# telem_board.net
KiCad netlist of a schematic drawn in EAGLE
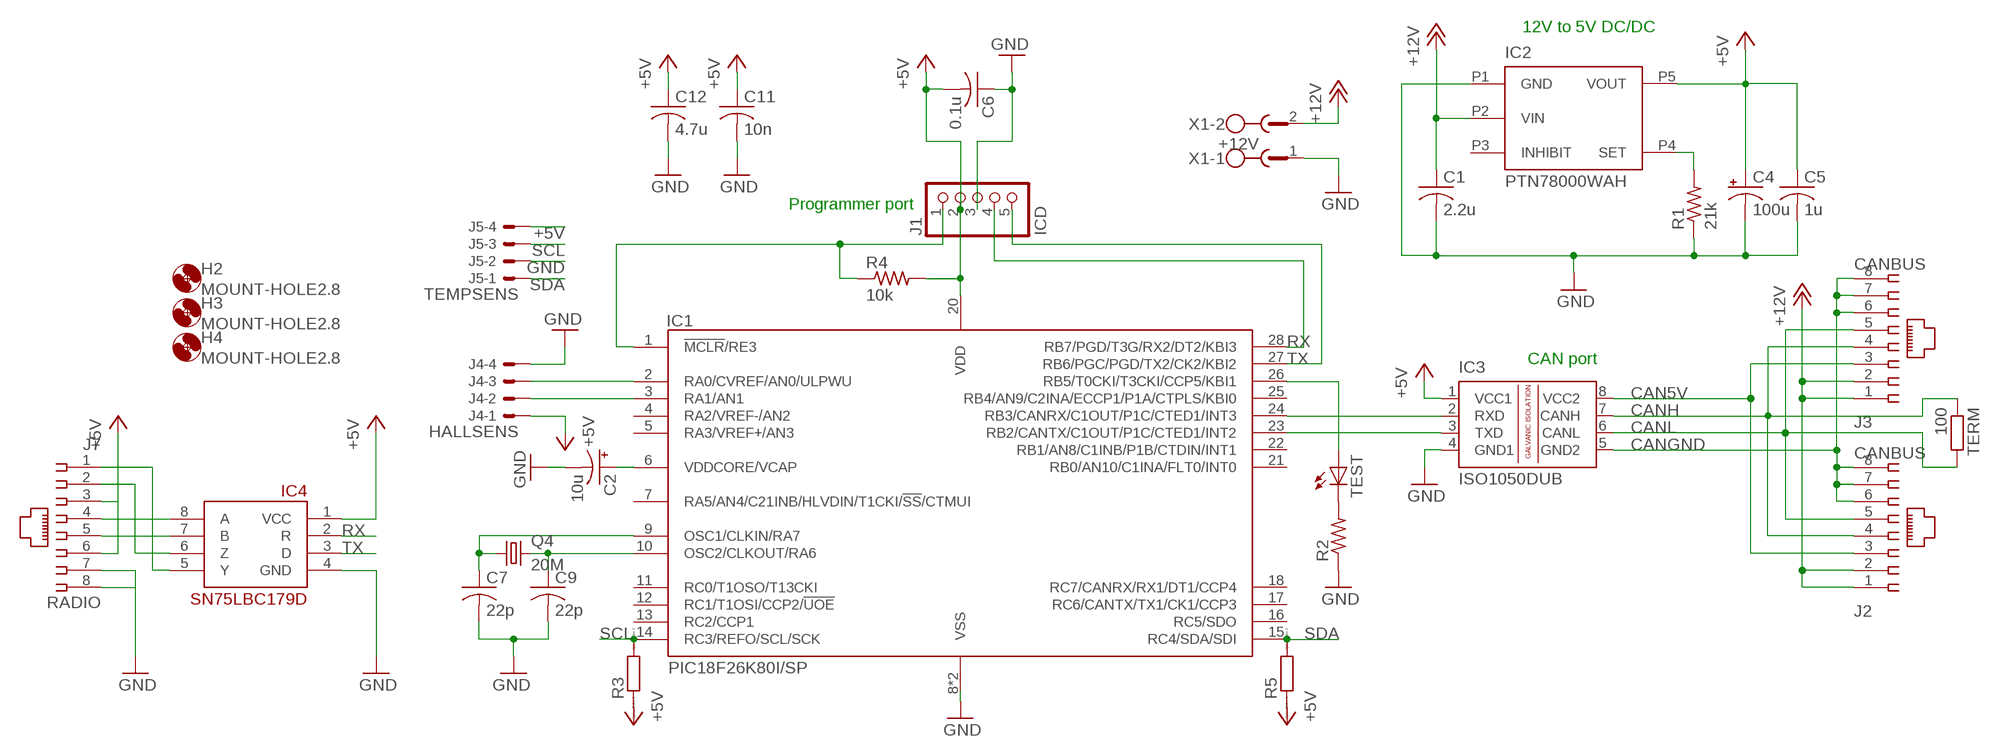
[diagram p0: schematic, sheet 1]

(export (version "E")
  (design (tool "Eeschema 10.0.6"))
  (components
    (comp (ref "C1")
      (value "2.2u")
      (footprint "eagle-import:C1206")
      (libsource (lib "eagle-import") (part "C-USC1206"))
    )
    (comp (ref "C2")
      (value "10u")
      (footprint "eagle-import:TT2D4")
      (libsource (lib "eagle-import") (part "CPOL-USTT2D4"))
    )
    (comp (ref "C4")
      (value "100u")
      (footprint "eagle-import:SMC_D")
      (libsource (lib "eagle-import") (part "CPOL-USSMCD"))
    )
    (comp (ref "C5")
      (value "1u")
      (footprint "eagle-import:C0805")
      (libsource (lib "eagle-import") (part "C-USC0805"))
    )
    (comp (ref "C6")
      (value "0.1u")
      (footprint "eagle-import:C0805")
      (libsource (lib "eagle-import") (part "C-USC0805"))
    )
    (comp (ref "C7")
      (value "22p")
      (footprint "eagle-import:C0805")
      (libsource (lib "eagle-import") (part "C-USC0805"))
    )
    (comp (ref "C9")
      (value "22p")
      (footprint "eagle-import:C0805")
      (libsource (lib "eagle-import") (part "C-USC0805"))
    )
    (comp (ref "C11")
      (value "10n")
      (footprint "eagle-import:C0805")
      (libsource (lib "eagle-import") (part "resistor_C-USC0805"))
    )
    (comp (ref "C12")
      (value "4.7u")
      (footprint "eagle-import:C0805")
      (libsource (lib "eagle-import") (part "resistor_C-USC0805"))
    )
    (comp (ref "H2")
      (value "MOUNT-HOLE2.8")
      (footprint "eagle-import:2,8")
      (libsource (lib "eagle-import") (part "MOUNT-HOLE2.8"))
    )
    (comp (ref "H3")
      (value "MOUNT-HOLE2.8")
      (footprint "eagle-import:2,8")
      (libsource (lib "eagle-import") (part "MOUNT-HOLE2.8"))
    )
    (comp (ref "H4")
      (value "MOUNT-HOLE2.8")
      (footprint "eagle-import:2,8")
      (libsource (lib "eagle-import") (part "MOUNT-HOLE2.8"))
    )
    (comp (ref "IC1")
      (value "PIC18F26K80I/SP")
      (footprint "eagle-import:DIL28_3")
      (libsource (lib "eagle-import") (part "PIC18F26K80I/SP"))
    )
    (comp (ref "IC2")
      (value "PTN78000WAH")
      (footprint "eagle-import:PTN78000")
      (libsource (lib "eagle-import") (part "PTN78000WAH"))
    )
    (comp (ref "IC3")
      (value "ISO1050DUB")
      (footprint "eagle-import:DUB-R-PDSO-G8")
      (fields (field (name "MPN") "ISO1050DUBR"))
      (libsource (lib "eagle-import") (part "ISO1050DUB"))
    )
    (comp (ref "IC4")
      (value "SN75LBC179D")
      (footprint "eagle-import:SO08")
      (libsource (lib "eagle-import") (part "SN75LBC179D"))
    )
    (comp (ref "J1")
      (value "ICD")
      (footprint "eagle-import:1X05")
      (libsource (lib "eagle-import") (part "PINHD-1X5"))
    )
    (comp (ref "J2")
      (value "CANBUS")
      (footprint "eagle-import:215877-7")
      (libsource (lib "eagle-import") (part "215877-7"))
    )
    (comp (ref "J3")
      (value "CANBUS")
      (footprint "eagle-import:215877-7")
      (libsource (lib "eagle-import") (part "215877-7"))
    )
    (comp (ref "J4")
      (value "HALLSENS")
      (footprint "eagle-import:6410-04")
      (libsource (lib "eagle-import") (part "22-?-0427-2041"))
    )
    (comp (ref "J5")
      (value "TEMPSENS")
      (footprint "eagle-import:6410-04")
      (libsource (lib "eagle-import") (part "22-?-0427-2041"))
    )
    (comp (ref "J7")
      (value "RADIO")
      (footprint "eagle-import:215877-7")
      (libsource (lib "eagle-import") (part "215877-7"))
    )
    (comp (ref "Q4")
      (value "20M")
      (footprint "eagle-import:HC49_S")
      (libsource (lib "eagle-import") (part "CRYSTALHC49S"))
    )
    (comp (ref "R1")
      (value "21k")
      (footprint "eagle-import:R0805")
      (libsource (lib "eagle-import") (part "rcl_R-US_R0805"))
    )
    (comp (ref "R2")
      (value "R-US_R0805")
      (footprint "eagle-import:R0805")
      (libsource (lib "eagle-import") (part "R-US_R0805"))
    )
    (comp (ref "R3") (value "R") (footprint "eagle-import:R0805") (libsource (lib "eagle-import") (part "R")))
    (comp (ref "R4")
      (value "10k")
      (footprint "eagle-import:R0805")
      (libsource (lib "eagle-import") (part "rcl_R-US_R0805"))
    )
    (comp (ref "R5") (value "R") (footprint "eagle-import:R0805") (libsource (lib "eagle-import") (part "R")))
    (comp (ref "TERM")
      (value "100")
      (footprint "eagle-import:0207_10")
      (libsource (lib "eagle-import") (part "R-EU_0207/10"))
    )
    (comp (ref "TEST")
      (value "LED5MM")
      (footprint "eagle-import:LED5MM")
      (libsource (lib "eagle-import") (part "LED5MM"))
    )
    (comp (ref "X1")
      (value "+12V")
      (footprint "eagle-import:MSTBA2")
      (fields (field (name "MF") "FARNELL") (field (name "MPN") "1757242"))
      (libsource (lib "eagle-import") (part "MSTBA2"))
    )
  )
  (nets
    (net (code "1") (name "+5V") (class "Default")
      (node (ref "C11") (pin "1") (pinfunction "1_1") (pintype "passive"))
      (node (ref "C12") (pin "1") (pinfunction "1_1") (pintype "passive"))
      (node (ref "C4") (pin "+") (pinfunction "+_+") (pintype "passive"))
      (node (ref "C5") (pin "1") (pinfunction "1_1") (pintype "passive"))
      (node (ref "C6") (pin "2") (pinfunction "2_2") (pintype "passive"))
      (node (ref "IC1") (pin "20") (pinfunction "VDD_20") (pintype "power_in"))
      (node (ref "IC2") (pin "P5") (pinfunction "VOUT_P5") (pintype "power_in"))
      (node (ref "IC3") (pin "1") (pinfunction "VCC1_1") (pintype "input"))
      (node (ref "IC4") (pin "1") (pinfunction "VCC_1") (pintype "power_in"))
      (node (ref "J1") (pin "2") (pinfunction "2_2") (pintype "passive"))
      (node (ref "J4") (pin "1") (pinfunction "S_1") (pintype "passive"))
      (node (ref "J5") (pin "4") (pinfunction "S_4") (pintype "passive"))
      (node (ref "J7") (pin "3") (pinfunction "3_3") (pintype "passive"))
      (node (ref "J7") (pin "6") (pinfunction "6_6") (pintype "passive"))
      (node (ref "R3") (pin "1") (pinfunction "1_1") (pintype "passive"))
      (node (ref "R4") (pin "2") (pinfunction "2_2") (pintype "passive"))
      (node (ref "R5") (pin "1") (pinfunction "1_1") (pintype "passive"))
    )
    (net (code "2") (name "+12V") (class "Default")
      (node (ref "C1") (pin "1") (pinfunction "1_1") (pintype "passive"))
      (node (ref "IC2") (pin "P2") (pinfunction "VIN_P2") (pintype "power_in"))
      (node (ref "J2") (pin "1") (pinfunction "1_1") (pintype "passive"))
      (node (ref "J2") (pin "2") (pinfunction "2_2") (pintype "passive"))
      (node (ref "J3") (pin "1") (pinfunction "1_1") (pintype "passive"))
      (node (ref "J3") (pin "2") (pinfunction "2_2") (pintype "passive"))
      (node (ref "X1") (pin "2") (pinfunction "1_2") (pintype "passive"))
    )
    (net (code "3") (name "/CAN5V") (class "Default")
      (node (ref "IC3") (pin "8") (pinfunction "VCC2_8") (pintype "input"))
      (node (ref "J2") (pin "3") (pinfunction "3_3") (pintype "passive"))
      (node (ref "J3") (pin "3") (pinfunction "3_3") (pintype "passive"))
    )
    (net (code "4") (name "/CANGND") (class "Default")
      (node (ref "IC3") (pin "5") (pinfunction "GND2_5") (pintype "input"))
      (node (ref "J2") (pin "6") (pinfunction "6_6") (pintype "passive"))
      (node (ref "J2") (pin "7") (pinfunction "7_7") (pintype "passive"))
      (node (ref "J2") (pin "8") (pinfunction "8_8") (pintype "passive"))
      (node (ref "J3") (pin "6") (pinfunction "6_6") (pintype "passive"))
      (node (ref "J3") (pin "7") (pinfunction "7_7") (pintype "passive"))
      (node (ref "J3") (pin "8") (pinfunction "8_8") (pintype "passive"))
    )
    (net (code "5") (name "/CANH") (class "Default")
      (node (ref "IC3") (pin "7") (pinfunction "CANH_7") (pintype "input"))
      (node (ref "J2") (pin "4") (pinfunction "4_4") (pintype "passive"))
      (node (ref "J3") (pin "4") (pinfunction "4_4") (pintype "passive"))
      (node (ref "TERM") (pin "1") (pinfunction "1_1") (pintype "passive"))
    )
    (net (code "6") (name "/CANL") (class "Default")
      (node (ref "IC3") (pin "6") (pinfunction "CANL_6") (pintype "input"))
      (node (ref "J2") (pin "5") (pinfunction "5_5") (pintype "passive"))
      (node (ref "J3") (pin "5") (pinfunction "5_5") (pintype "passive"))
      (node (ref "TERM") (pin "2") (pinfunction "2_2") (pintype "passive"))
    )
    (net (code "7") (name "/RX") (class "Default")
      (node (ref "IC1") (pin "28") (pinfunction "RB7/PGD/T3G/RX2/DT2/KBI3_28") (pintype "bidirectional"))
      (node (ref "IC4") (pin "2") (pinfunction "R_2") (pintype "output"))
      (node (ref "J1") (pin "4") (pinfunction "4_4") (pintype "passive"))
    )
    (net (code "8") (name "/SCL") (class "Default")
      (node (ref "IC1") (pin "14") (pinfunction "RC3/REFO/SCL/SCK_14") (pintype "bidirectional"))
      (node (ref "J5") (pin "3") (pinfunction "S_3") (pintype "passive"))
      (node (ref "R3") (pin "2") (pinfunction "2_2") (pintype "passive"))
    )
    (net (code "9") (name "/SDA") (class "Default")
      (node (ref "IC1") (pin "15") (pinfunction "RC4/SDA/SDI_15") (pintype "bidirectional"))
      (node (ref "J5") (pin "1") (pinfunction "S_1") (pintype "passive"))
      (node (ref "R5") (pin "2") (pinfunction "2_2") (pintype "passive"))
    )
    (net (code "10") (name "/TX") (class "Default")
      (node (ref "IC1") (pin "27") (pinfunction "RB6/PGC/PGD/TX2/CK2/KBI2_27") (pintype "bidirectional"))
      (node (ref "IC4") (pin "3") (pinfunction "D_3") (pintype "input"))
      (node (ref "J1") (pin "5") (pinfunction "5_5") (pintype "passive"))
    )
    (net (code "11") (name "GND") (class "Default")
      (node (ref "C1") (pin "2") (pinfunction "2_2") (pintype "passive"))
      (node (ref "C11") (pin "2") (pinfunction "2_2") (pintype "passive"))
      (node (ref "C12") (pin "2") (pinfunction "2_2") (pintype "passive"))
      (node (ref "C2") (pin "-") (pinfunction "-_-") (pintype "passive"))
      (node (ref "C4") (pin "-") (pinfunction "-_-") (pintype "passive"))
      (node (ref "C5") (pin "2") (pinfunction "2_2") (pintype "passive"))
      (node (ref "C6") (pin "1") (pinfunction "1_1") (pintype "passive"))
      (node (ref "C7") (pin "2") (pinfunction "2_2") (pintype "passive"))
      (node (ref "C9") (pin "2") (pinfunction "2_2") (pintype "passive"))
      (node (ref "IC1") (pin "19") (pinfunction "VSS_19") (pintype "power_in"))
      (node (ref "IC1") (pin "8") (pinfunction "VSS_8") (pintype "power_in"))
      (node (ref "IC2") (pin "P1") (pinfunction "GND_P1") (pintype "power_in"))
      (node (ref "IC3") (pin "4") (pinfunction "GND1_4") (pintype "input"))
      (node (ref "IC4") (pin "4") (pinfunction "GND_4") (pintype "power_in"))
      (node (ref "J1") (pin "3") (pinfunction "3_3") (pintype "passive"))
      (node (ref "J4") (pin "4") (pinfunction "S_4") (pintype "passive"))
      (node (ref "J5") (pin "2") (pinfunction "S_2") (pintype "passive"))
      (node (ref "J7") (pin "7") (pinfunction "7_7") (pintype "passive"))
      (node (ref "J7") (pin "8") (pinfunction "8_8") (pintype "passive"))
      (node (ref "R1") (pin "1") (pinfunction "1_1") (pintype "passive"))
      (node (ref "R2") (pin "1") (pinfunction "1_1") (pintype "passive"))
      (node (ref "X1") (pin "1") (pinfunction "1_1") (pintype "passive"))
    )
    (net (code "12") (name "Net-(IC1-OSC1{slash}CLKIN{slash}RA7)") (class "Default")
      (node (ref "C7") (pin "1") (pinfunction "1_1") (pintype "passive"))
      (node (ref "IC1") (pin "9") (pinfunction "OSC1/CLKIN/RA7_9") (pintype "bidirectional"))
      (node (ref "Q4") (pin "1") (pinfunction "1_1") (pintype "passive"))
    )
    (net (code "13") (name "Net-(IC1-OSC2{slash}CLKOUT{slash}RA6)") (class "Default")
      (node (ref "C9") (pin "1") (pinfunction "1_1") (pintype "passive"))
      (node (ref "IC1") (pin "10") (pinfunction "OSC2/CLKOUT/RA6_10") (pintype "bidirectional"))
      (node (ref "Q4") (pin "2") (pinfunction "2_2") (pintype "passive"))
    )
    (net (code "14") (name "Net-(IC1-RA0{slash}CVREF{slash}AN0{slash}ULPWU)") (class "Default")
      (node (ref "IC1") (pin "2") (pinfunction "RA0/CVREF/AN0/ULPWU_2") (pintype "bidirectional"))
      (node (ref "J4") (pin "3") (pinfunction "S_3") (pintype "passive"))
    )
    (net (code "15") (name "Net-(IC1-RA1{slash}AN1)") (class "Default")
      (node (ref "IC1") (pin "3") (pinfunction "RA1/AN1_3") (pintype "bidirectional"))
      (node (ref "J4") (pin "2") (pinfunction "S_2") (pintype "passive"))
    )
    (net (code "16") (name "Net-(IC1-RB2{slash}CANTX{slash}C1OUT{slash}P1C{slash}CTED1{slash}INT2)") (class "Default")
      (node (ref "IC1") (pin "23") (pinfunction "RB2/CANTX/C1OUT/P1C/CTED1/INT2_23") (pintype "bidirectional"))
      (node (ref "IC3") (pin "3") (pinfunction "TXD_3") (pintype "input"))
    )
    (net (code "17") (name "Net-(IC1-RB3{slash}CANRX{slash}C1OUT{slash}P1C{slash}CTED1{slash}INT3)") (class "Default")
      (node (ref "IC1") (pin "24") (pinfunction "RB3/CANRX/C1OUT/P1C/CTED1/INT3_24") (pintype "bidirectional"))
      (node (ref "IC3") (pin "2") (pinfunction "RXD_2") (pintype "input"))
    )
    (net (code "18") (name "Net-(IC1-RB5{slash}T0CKI{slash}T3CKI{slash}CCP5{slash}KBI1)") (class "Default")
      (node (ref "IC1") (pin "26") (pinfunction "RB5/T0CKI/T3CKI/CCP5/KBI1_26") (pintype "bidirectional"))
      (node (ref "TEST") (pin "A") (pinfunction "A_A") (pintype "passive"))
    )
    (net (code "19") (name "Net-(IC1-VDDCORE{slash}VCAP)") (class "Default")
      (node (ref "C2") (pin "+") (pinfunction "+_+") (pintype "passive"))
      (node (ref "IC1") (pin "6") (pinfunction "VDDCORE/VCAP_6") (pintype "bidirectional"))
    )
    (net (code "20") (name "Net-(IC1-~{MCLR}{slash}RE3)") (class "Default")
      (node (ref "IC1") (pin "1") (pinfunction "~{MCLR}/RE3_1") (pintype "input"))
      (node (ref "J1") (pin "1") (pinfunction "1_1") (pintype "passive"))
      (node (ref "R4") (pin "1") (pinfunction "1_1") (pintype "passive"))
    )
    (net (code "21") (name "Net-(IC2-SET)") (class "Default")
      (node (ref "IC2") (pin "P4") (pinfunction "SET_P4") (pintype "bidirectional"))
      (node (ref "R1") (pin "2") (pinfunction "2_2") (pintype "passive"))
    )
    (net (code "22") (name "Net-(IC4-A)") (class "Default")
      (node (ref "IC4") (pin "8") (pinfunction "A_8") (pintype "input"))
      (node (ref "J7") (pin "4") (pinfunction "4_4") (pintype "passive"))
    )
    (net (code "23") (name "Net-(IC4-B)") (class "Default")
      (node (ref "IC4") (pin "7") (pinfunction "B_7") (pintype "input"))
      (node (ref "J7") (pin "5") (pinfunction "5_5") (pintype "passive"))
    )
    (net (code "24") (name "Net-(IC4-Y)") (class "Default")
      (node (ref "IC4") (pin "5") (pinfunction "Y_5") (pintype "output"))
      (node (ref "J7") (pin "1") (pinfunction "1_1") (pintype "passive"))
    )
    (net (code "25") (name "Net-(IC4-Z)") (class "Default")
      (node (ref "IC4") (pin "6") (pinfunction "Z_6") (pintype "output"))
      (node (ref "J7") (pin "2") (pinfunction "2_2") (pintype "passive"))
    )
    (net (code "26") (name "Net-(TEST-C)") (class "Default")
      (node (ref "R2") (pin "2") (pinfunction "2_2") (pintype "passive"))
      (node (ref "TEST") (pin "K") (pinfunction "C_K") (pintype "passive"))
    )
    (net (code "27") (name "unconnected-(IC1-RA2{slash}VREF-{slash}AN2-Pad4)") (class "Default")
      (node (ref "IC1") (pin "4") (pinfunction "RA2/VREF-/AN2_4") (pintype "bidirectional"))
    )
    (net (code "28") (name "unconnected-(IC1-RA3{slash}VREF+{slash}AN3-Pad5)") (class "Default")
      (node (ref "IC1") (pin "5") (pinfunction "RA3/VREF+/AN3_5") (pintype "bidirectional"))
    )
    (net (code "29") (name "unconnected-(IC1-RA5{slash}AN4{slash}C21INB{slash}HLVDIN{slash}T1CKI{slash}~{SS}{slash}CTMUI-Pad7)") (class "Default")
      (node (ref "IC1") (pin "7") (pinfunction "RA5/AN4/C21INB/HLVDIN/T1CKI/~{SS}/CTMUI_7") (pintype "bidirectional"))
    )
    (net (code "30") (name "unconnected-(IC1-RB0{slash}AN10{slash}C1INA{slash}FLT0{slash}INT0-Pad21)") (class "Default")
      (node (ref "IC1") (pin "21") (pinfunction "RB0/AN10/C1INA/FLT0/INT0_21") (pintype "bidirectional"))
    )
    (net (code "31") (name "unconnected-(IC1-RB1{slash}AN8{slash}C1INB{slash}P1B{slash}CTDIN{slash}INT1-Pad22)") (class "Default")
      (node (ref "IC1") (pin "22") (pinfunction "RB1/AN8/C1INB/P1B/CTDIN/INT1_22") (pintype "bidirectional"))
    )
    (net (code "32") (name "unconnected-(IC1-RB4{slash}AN9{slash}C2INA{slash}ECCP1{slash}P1A{slash}CTPLS{slash}KBI0-Pad25)") (class "Default")
      (node (ref "IC1") (pin "25") (pinfunction "RB4/AN9/C2INA/ECCP1/P1A/CTPLS/KBI0_25") (pintype "bidirectional"))
    )
    (net (code "33") (name "unconnected-(IC1-RC0{slash}T1OSO{slash}T13CKI-Pad11)") (class "Default")
      (node (ref "IC1") (pin "11") (pinfunction "RC0/T1OSO/T13CKI_11") (pintype "bidirectional"))
    )
    (net (code "34") (name "unconnected-(IC1-RC1{slash}T1OSI{slash}CCP2{slash}~{UOE}-Pad12)") (class "Default")
      (node (ref "IC1") (pin "12") (pinfunction "RC1/T1OSI/CCP2/~{UOE}_12") (pintype "bidirectional"))
    )
    (net (code "35") (name "unconnected-(IC1-RC2{slash}CCP1-Pad13)") (class "Default")
      (node (ref "IC1") (pin "13") (pinfunction "RC2/CCP1_13") (pintype "bidirectional"))
    )
    (net (code "36") (name "unconnected-(IC1-RC5{slash}SDO-Pad16)") (class "Default")
      (node (ref "IC1") (pin "16") (pinfunction "RC5/SDO_16") (pintype "bidirectional"))
    )
    (net (code "37") (name "unconnected-(IC1-RC6{slash}CANTX{slash}TX1{slash}CK1{slash}CCP3-Pad17)") (class "Default")
      (node (ref "IC1") (pin "17") (pinfunction "RC6/CANTX/TX1/CK1/CCP3_17") (pintype "bidirectional"))
    )
    (net (code "38") (name "unconnected-(IC1-RC7{slash}CANRX{slash}RX1{slash}DT1{slash}CCP4-Pad18)") (class "Default")
      (node (ref "IC1") (pin "18") (pinfunction "RC7/CANRX/RX1/DT1/CCP4_18") (pintype "bidirectional"))
    )
    (net (code "39") (name "unconnected-(IC2-INHIBIT-PadP3)") (class "Default")
      (node (ref "IC2") (pin "P3") (pinfunction "INHIBIT_P3") (pintype "bidirectional"))
    )
  )
)
